# power_sml_pcb.net
KiCad netlist of a schematic drawn in EAGLE
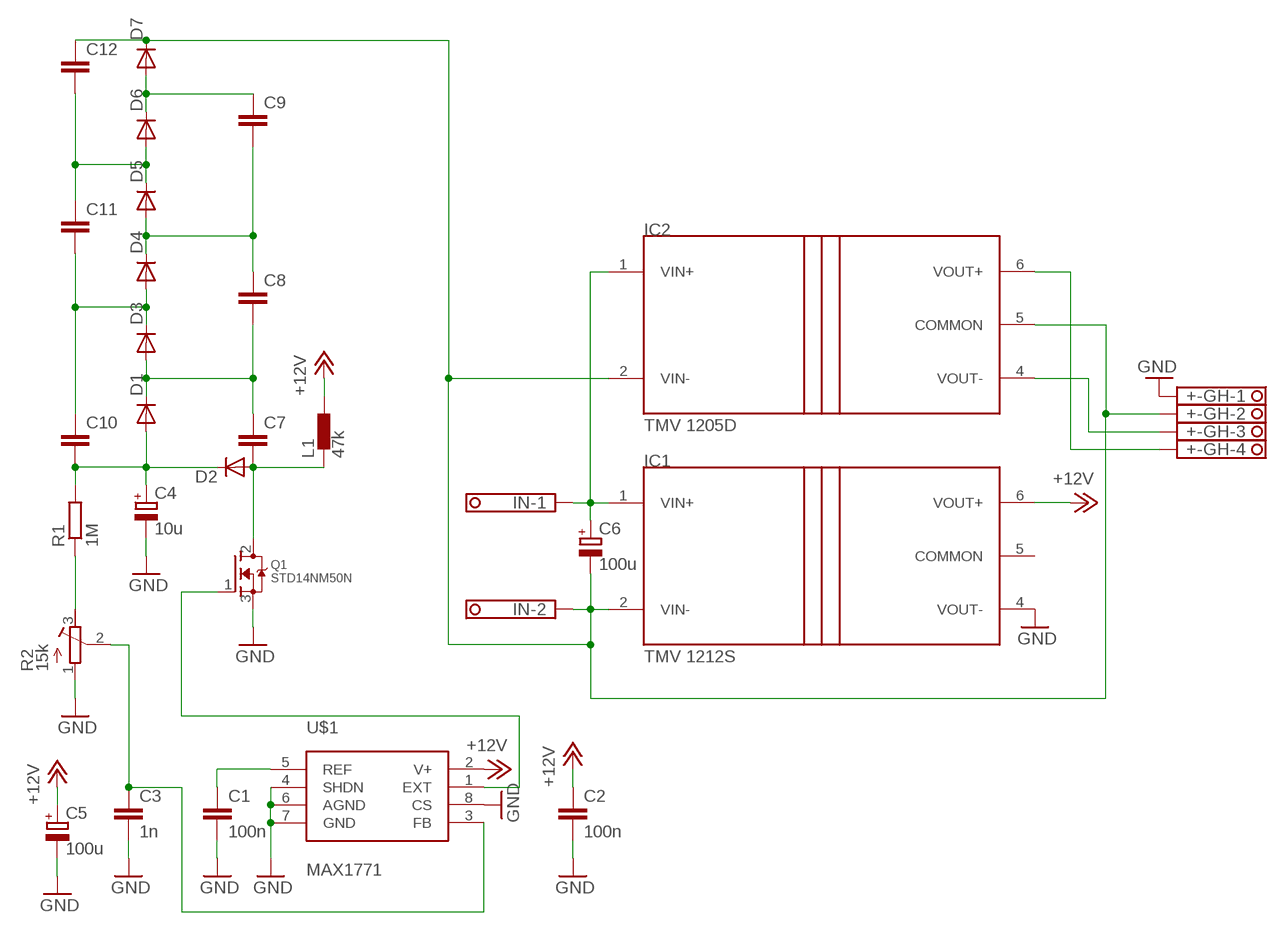
[diagram p0: schematic, sheet 1]

(export (version "E")
  (design (tool "Eeschema 10.0.6"))
  (components
    (comp (ref "+-GH")
      (value "1751264")
      (footprint "eagle-import:1751264")
      (libsource (lib "eagle-import") (part "1751264"))
    )
    (comp (ref "C1")
      (value "100n")
      (footprint "eagle-import:C0603")
      (libsource (lib "eagle-import") (part "C-EUC0603"))
    )
    (comp (ref "C2")
      (value "100n")
      (footprint "eagle-import:C0603")
      (libsource (lib "eagle-import") (part "C-EUC0603"))
    )
    (comp (ref "C3")
      (value "1n")
      (footprint "eagle-import:C0603")
      (libsource (lib "eagle-import") (part "C-EUC0603"))
    )
    (comp (ref "C4")
      (value "10u")
      (footprint "eagle-import:E5-10,5")
      (libsource (lib "eagle-import") (part "CPOL-EUE5-10.5"))
    )
    (comp (ref "C5")
      (value "100u")
      (footprint "eagle-import:SMC_C")
      (libsource (lib "eagle-import") (part "CPOL-EUSMCC"))
    )
    (comp (ref "C6")
      (value "100u")
      (footprint "eagle-import:E2,5-6")
      (libsource (lib "eagle-import") (part "CPOL-EUE2.5-6"))
    )
    (comp (ref "C7")
      (value "C-EU102-054X133")
      (footprint "eagle-import:C102-054X133")
      (libsource (lib "eagle-import") (part "C-EU102-054X133"))
    )
    (comp (ref "C8")
      (value "C-EU102-054X133")
      (footprint "eagle-import:C102-054X133")
      (libsource (lib "eagle-import") (part "C-EU102-054X133"))
    )
    (comp (ref "C9")
      (value "C-EU102-054X133")
      (footprint "eagle-import:C102-054X133")
      (libsource (lib "eagle-import") (part "C-EU102-054X133"))
    )
    (comp (ref "C10")
      (value "C-EU102-054X133")
      (footprint "eagle-import:C102-054X133")
      (libsource (lib "eagle-import") (part "C-EU102-054X133"))
    )
    (comp (ref "C11")
      (value "C-EU102-054X133")
      (footprint "eagle-import:C102-054X133")
      (libsource (lib "eagle-import") (part "C-EU102-054X133"))
    )
    (comp (ref "C12")
      (value "C-EU102-054X133")
      (footprint "eagle-import:C102-054X133")
      (libsource (lib "eagle-import") (part "C-EU102-054X133"))
    )
    (comp (ref "D1")
      (value "DIODE-DO214AA")
      (footprint "eagle-import:DO214AA")
      (libsource (lib "eagle-import") (part "DIODE-DO214AA"))
    )
    (comp (ref "D2")
      (value "DIODE-DO214AA")
      (footprint "eagle-import:DO214AA")
      (libsource (lib "eagle-import") (part "DIODE-DO214AA"))
    )
    (comp (ref "D3")
      (value "DIODE-DO214AA")
      (footprint "eagle-import:DO214AA")
      (libsource (lib "eagle-import") (part "DIODE-DO214AA"))
    )
    (comp (ref "D4")
      (value "DIODE-DO214AA")
      (footprint "eagle-import:DO214AA")
      (libsource (lib "eagle-import") (part "DIODE-DO214AA"))
    )
    (comp (ref "D5")
      (value "DIODE-DO214AA")
      (footprint "eagle-import:DO214AA")
      (libsource (lib "eagle-import") (part "DIODE-DO214AA"))
    )
    (comp (ref "D6")
      (value "DIODE-DO214AA")
      (footprint "eagle-import:DO214AA")
      (libsource (lib "eagle-import") (part "DIODE-DO214AA"))
    )
    (comp (ref "D7")
      (value "DIODE-DO214AA")
      (footprint "eagle-import:DO214AA")
      (libsource (lib "eagle-import") (part "DIODE-DO214AA"))
    )
    (comp (ref "IC1")
      (value "TMV 1212S")
      (footprint "eagle-import:SIP7")
      (libsource (lib "eagle-import") (part "TMA1212S"))
    )
    (comp (ref "IC2")
      (value "TMV 1205D")
      (footprint "eagle-import:SIP7")
      (libsource (lib "eagle-import") (part "TMA0505D"))
    )
    (comp (ref "IN")
      (value "1751248")
      (footprint "eagle-import:1751248")
      (libsource (lib "eagle-import") (part "1751248"))
    )
    (comp (ref "L1")
      (value "47k")
      (footprint "eagle-import:DR1030")
      (libsource (lib "eagle-import") (part "DR1030"))
    )
    (comp (ref "Q1")
      (value "STD14NM50N")
      (footprint "eagle-import:DPAK")
      (libsource (lib "eagle-import") (part "NFET_DPAK"))
    )
    (comp (ref "R1")
      (value "1M")
      (footprint "eagle-import:0207_7")
      (libsource (lib "eagle-import") (part "R-EU_0207/7"))
    )
    (comp (ref "R2")
      (value "15k")
      (footprint "eagle-import:RTRIM3296W")
      (libsource (lib "eagle-import") (part "R-TRIMM3296W"))
    )
    (comp (ref "U$1")
      (value "MAX1771")
      (footprint "eagle-import:SOIC8")
      (libsource (lib "eagle-import") (part "MAX1771-SOIC8"))
    )
  )
  (nets
    (net (code "1") (name "+12V") (class "Default")
      (node (ref "C2") (pin "1") (pinfunction "1_1") (pintype "passive"))
      (node (ref "C5") (pin "+") (pinfunction "+_+") (pintype "passive"))
      (node (ref "IC1") (pin "6") (pinfunction "VOUT+_6") (pintype "power_in"))
      (node (ref "L1") (pin "2") (pinfunction "2_2") (pintype "passive"))
      (node (ref "U$1") (pin "2") (pinfunction "V+_2") (pintype "bidirectional"))
    )
    (net (code "2") (name "/COMMON") (class "Default")
      (node (ref "IC1") (pin "5") (pinfunction "COMMON_5") (pintype "power_in"))
    )
    (net (code "3") (name "GND") (class "Default")
      (node (ref "+-GH") (pin "1") (pinfunction "K_1") (pintype "passive"))
      (node (ref "C1") (pin "2") (pinfunction "2_2") (pintype "passive"))
      (node (ref "C2") (pin "2") (pinfunction "2_2") (pintype "passive"))
      (node (ref "C3") (pin "2") (pinfunction "2_2") (pintype "passive"))
      (node (ref "C4") (pin "-") (pinfunction "-_-") (pintype "passive"))
      (node (ref "C5") (pin "-") (pinfunction "-_-") (pintype "passive"))
      (node (ref "IC1") (pin "4") (pinfunction "VOUT-_4") (pintype "power_in"))
      (node (ref "Q1") (pin "3") (pinfunction "S_3") (pintype "bidirectional"))
      (node (ref "R2") (pin "1") (pinfunction "E_1") (pintype "passive"))
      (node (ref "U$1") (pin "4") (pinfunction "SHDN_4") (pintype "bidirectional"))
      (node (ref "U$1") (pin "6") (pinfunction "AGND_6") (pintype "bidirectional"))
      (node (ref "U$1") (pin "7") (pinfunction "GND_7") (pintype "bidirectional"))
      (node (ref "U$1") (pin "8") (pinfunction "CS_8") (pintype "bidirectional"))
    )
    (net (code "4") (name "Net-(+-GHB-K)") (class "Default")
      (node (ref "+-GH") (pin "2") (pinfunction "K_2") (pintype "passive"))
      (node (ref "C12") (pin "1") (pinfunction "1_1") (pintype "passive"))
      (node (ref "C6") (pin "-") (pinfunction "-_-") (pintype "passive"))
      (node (ref "D7") (pin "C") (pinfunction "C_C") (pintype "passive"))
      (node (ref "IC1") (pin "2") (pinfunction "VIN-_2") (pintype "power_in"))
      (node (ref "IC2") (pin "2") (pinfunction "VIN-_2") (pintype "power_in"))
      (node (ref "IC2") (pin "5") (pinfunction "COMMON_5") (pintype "power_in"))
      (node (ref "IN") (pin "2") (pinfunction "K_2") (pintype "passive"))
    )
    (net (code "5") (name "Net-(+-GHC-K)") (class "Default")
      (node (ref "+-GH") (pin "3") (pinfunction "K_3") (pintype "passive"))
      (node (ref "IC2") (pin "4") (pinfunction "VOUT-_4") (pintype "power_in"))
    )
    (net (code "6") (name "Net-(+-GHD-K)") (class "Default")
      (node (ref "+-GH") (pin "4") (pinfunction "K_4") (pintype "passive"))
      (node (ref "IC2") (pin "6") (pinfunction "VOUT+_6") (pintype "power_in"))
    )
    (net (code "7") (name "Net-(C7-Pad1)") (class "Default")
      (node (ref "C7") (pin "1") (pinfunction "1_1") (pintype "passive"))
      (node (ref "C8") (pin "2") (pinfunction "2_2") (pintype "passive"))
      (node (ref "D1") (pin "C") (pinfunction "C_C") (pintype "passive"))
      (node (ref "D3") (pin "A") (pinfunction "A_A") (pintype "passive"))
    )
    (net (code "8") (name "Net-(C8-Pad1)") (class "Default")
      (node (ref "C8") (pin "1") (pinfunction "1_1") (pintype "passive"))
      (node (ref "C9") (pin "2") (pinfunction "2_2") (pintype "passive"))
      (node (ref "D4") (pin "C") (pinfunction "C_C") (pintype "passive"))
      (node (ref "D5") (pin "A") (pinfunction "A_A") (pintype "passive"))
    )
    (net (code "9") (name "Net-(C9-Pad1)") (class "Default")
      (node (ref "C9") (pin "1") (pinfunction "1_1") (pintype "passive"))
      (node (ref "D6") (pin "C") (pinfunction "C_C") (pintype "passive"))
      (node (ref "D7") (pin "A") (pinfunction "A_A") (pintype "passive"))
    )
    (net (code "10") (name "Net-(C10-Pad1)") (class "Default")
      (node (ref "C10") (pin "1") (pinfunction "1_1") (pintype "passive"))
      (node (ref "C11") (pin "2") (pinfunction "2_2") (pintype "passive"))
      (node (ref "D3") (pin "C") (pinfunction "C_C") (pintype "passive"))
      (node (ref "D4") (pin "A") (pinfunction "A_A") (pintype "passive"))
    )
    (net (code "11") (name "Net-(C10-Pad2)") (class "Default")
      (node (ref "C10") (pin "2") (pinfunction "2_2") (pintype "passive"))
      (node (ref "C4") (pin "+") (pinfunction "+_+") (pintype "passive"))
      (node (ref "D1") (pin "A") (pinfunction "A_A") (pintype "passive"))
      (node (ref "D2") (pin "C") (pinfunction "C_C") (pintype "passive"))
      (node (ref "R1") (pin "2") (pinfunction "2_2") (pintype "passive"))
    )
    (net (code "12") (name "Net-(C11-Pad1)") (class "Default")
      (node (ref "C11") (pin "1") (pinfunction "1_1") (pintype "passive"))
      (node (ref "C12") (pin "2") (pinfunction "2_2") (pintype "passive"))
      (node (ref "D5") (pin "C") (pinfunction "C_C") (pintype "passive"))
      (node (ref "D6") (pin "A") (pinfunction "A_A") (pintype "passive"))
    )
    (net (code "13") (name "Net-(IC1-VIN+)") (class "Default")
      (node (ref "C6") (pin "+") (pinfunction "+_+") (pintype "passive"))
      (node (ref "IC1") (pin "1") (pinfunction "VIN+_1") (pintype "power_in"))
      (node (ref "IC2") (pin "1") (pinfunction "VIN+_1") (pintype "power_in"))
      (node (ref "IN") (pin "1") (pinfunction "K_1") (pintype "passive"))
    )
    (net (code "14") (name "Net-(Q1-D)") (class "Default")
      (node (ref "C7") (pin "2") (pinfunction "2_2") (pintype "passive"))
      (node (ref "D2") (pin "A") (pinfunction "A_A") (pintype "passive"))
      (node (ref "L1") (pin "1") (pinfunction "1_1") (pintype "passive"))
      (node (ref "Q1") (pin "2") (pinfunction "D_2") (pintype "bidirectional"))
    )
    (net (code "15") (name "Net-(Q1-G)") (class "Default")
      (node (ref "Q1") (pin "1") (pinfunction "G_1") (pintype "bidirectional"))
      (node (ref "U$1") (pin "1") (pinfunction "EXT_1") (pintype "bidirectional"))
    )
    (net (code "16") (name "Net-(R2-A)") (class "Default")
      (node (ref "R1") (pin "1") (pinfunction "1_1") (pintype "passive"))
      (node (ref "R2") (pin "3") (pinfunction "A_3") (pintype "passive"))
    )
    (net (code "17") (name "Net-(R2-S)") (class "Default")
      (node (ref "C3") (pin "1") (pinfunction "1_1") (pintype "passive"))
      (node (ref "R2") (pin "2") (pinfunction "S_2") (pintype "passive"))
      (node (ref "U$1") (pin "3") (pinfunction "FB_3") (pintype "bidirectional"))
    )
    (net (code "18") (name "Net-(U$1-REF)") (class "Default")
      (node (ref "C1") (pin "1") (pinfunction "1_1") (pintype "passive"))
      (node (ref "U$1") (pin "5") (pinfunction "REF_5") (pintype "bidirectional"))
    )
  )
)
